# Triangular_Wave.net
KiCad netlist of a schematic drawn in Altium Designer
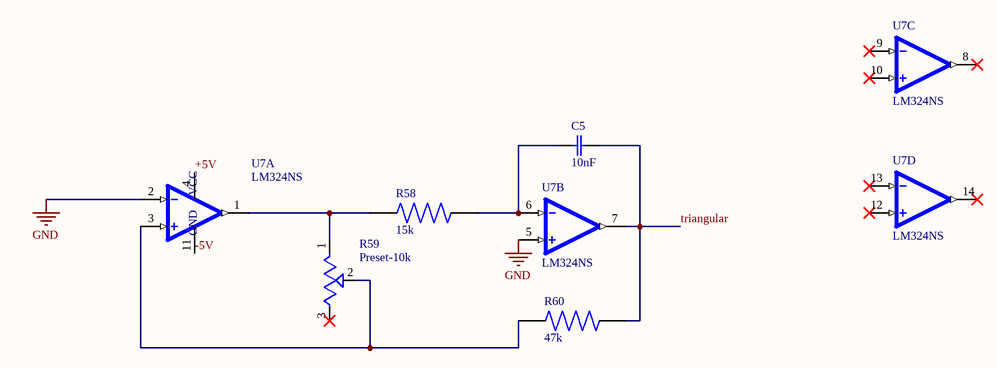
[diagram p0: Triangular_Wave.SchDoc]

(export (version "E")
  (design (tool "Eeschema 10.0.6"))
  (components
    (comp (ref "C5")
      (value "10nF")
      (footprint "CAPC2013X110N")
      (description "10000 pF Â±10% 50V Ceramic Capacitor X7R 0805 (2012 Metric); CC0805KRX7R9BB103")
      (fields (field (name "MF") "Yageo") (field (name "MP") "CC0805KRX7R9BB103"))
      (libsource (lib "10nfs") (part "10nF"))
    )
    (comp (ref "R58")
      (value "15k")
      (footprint "RES_ERA6ARB153V")
      (description "ERA6ARB153V")
      (libsource (lib "15ks") (part "15k"))
    )
    (comp (ref "R59")
      (value "Preset-10k")
      (footprint "TRIM_3306F-1-103")
      (description "TRIMMER - 6MM ROUND, SINGLE-TURN,CERMET, 10K OHMS ¦ Bourns 3306F-1-103")
      (fields (field (name "MF") "Bourns") (field (name "MP") "3306F-1-103"))
      (libsource (lib "3306F-1-103") (part "Preset"))
    )
    (comp (ref "R60")
      (value "47k")
      (footprint "RESC2012X60N")
      (fields (field (name "MF") "Yageo") (field (name "MP") "RC0805FR-0747KL"))
      (libsource (lib "47ks") (part "47k"))
    )
    (comp (ref "U7")
      (value "LM324NS")
      (footprint "SOIC127P780X200-14N")
      (description "4-Channel industry standard operational amplifier 14-SO 0 to 70; LM324NSRG4")
      (fields (field (name "MP") "LM324NSRG4") (field (name "MF") "Texas Instruments"))
      (libsource (lib "LM324NSRG4") (part "LM324NS"))
    )
  )
  (nets
    (net (code "1") (name "/+5V") (class "Default")
      (node (ref "U7") (pin "4") (pinfunction "VCC_4") (pintype "power_in"))
    )
    (net (code "2") (name "/-5V") (class "Default")
      (node (ref "U7") (pin "11") (pinfunction "GND_11") (pintype "power_in"))
    )
    (net (code "3") (name "/triangular") (class "Default")
      (node (ref "C5") (pin "2") (pinfunction "C2_2") (pintype "passive"))
      (node (ref "R60") (pin "2") (pinfunction "2_2") (pintype "passive"))
      (node (ref "U7") (pin "7") (pinfunction "2OUT_7") (pintype "output"))
    )
    (net (code "4") (name "GND") (class "Default")
      (node (ref "U7") (pin "2") (pinfunction "1IN-_2") (pintype "input"))
      (node (ref "U7") (pin "5") (pinfunction "2IN+_5") (pintype "input"))
    )
    (net (code "5") (name "Net-(C5-C1)") (class "Default")
      (node (ref "C5") (pin "1") (pinfunction "C1_1") (pintype "passive"))
      (node (ref "R58") (pin "2") (pinfunction "2_2") (pintype "passive"))
      (node (ref "U7") (pin "6") (pinfunction "2IN-_6") (pintype "input"))
    )
    (net (code "6") (name "Net-(R59-CCW)") (class "Default")
      (node (ref "R58") (pin "1") (pinfunction "1_1") (pintype "passive"))
      (node (ref "R59") (pin "1") (pinfunction "CCW_1") (pintype "passive"))
      (node (ref "U7") (pin "1") (pinfunction "1OUT_1") (pintype "output"))
    )
    (net (code "7") (name "Net-(R59-W)") (class "Default")
      (node (ref "R59") (pin "2") (pinfunction "W_2") (pintype "passive"))
      (node (ref "R60") (pin "1") (pinfunction "1_1") (pintype "passive"))
      (node (ref "U7") (pin "3") (pinfunction "1IN+_3") (pintype "input"))
    )
    (net (code "8") (name "unconnected-(R59-CW-Pad3)") (class "Default")
      (node (ref "R59") (pin "3") (pinfunction "CW_3") (pintype "passive+no_connect"))
    )
    (net (code "9") (name "unconnected-(U7C-3IN+-Pad10)") (class "Default")
      (node (ref "U7") (pin "10") (pinfunction "3IN+_10") (pintype "input+no_connect"))
    )
    (net (code "10") (name "unconnected-(U7C-3IN--Pad9)") (class "Default")
      (node (ref "U7") (pin "9") (pinfunction "3IN-_9") (pintype "input+no_connect"))
    )
    (net (code "11") (name "unconnected-(U7C-3OUT-Pad8)") (class "Default")
      (node (ref "U7") (pin "8") (pinfunction "3OUT_8") (pintype "output+no_connect"))
    )
    (net (code "12") (name "unconnected-(U7D-4IN+-Pad12)") (class "Default")
      (node (ref "U7") (pin "12") (pinfunction "4IN+_12") (pintype "input+no_connect"))
    )
    (net (code "13") (name "unconnected-(U7D-4IN--Pad13)") (class "Default")
      (node (ref "U7") (pin "13") (pinfunction "4IN-_13") (pintype "input+no_connect"))
    )
    (net (code "14") (name "unconnected-(U7D-4OUT-Pad14)") (class "Default")
      (node (ref "U7") (pin "14") (pinfunction "4OUT_14") (pintype "output+no_connect"))
    )
  )
)
